# Acionadores_e_Atuadores.net
KiCad netlist of a schematic drawn in Altium Designer
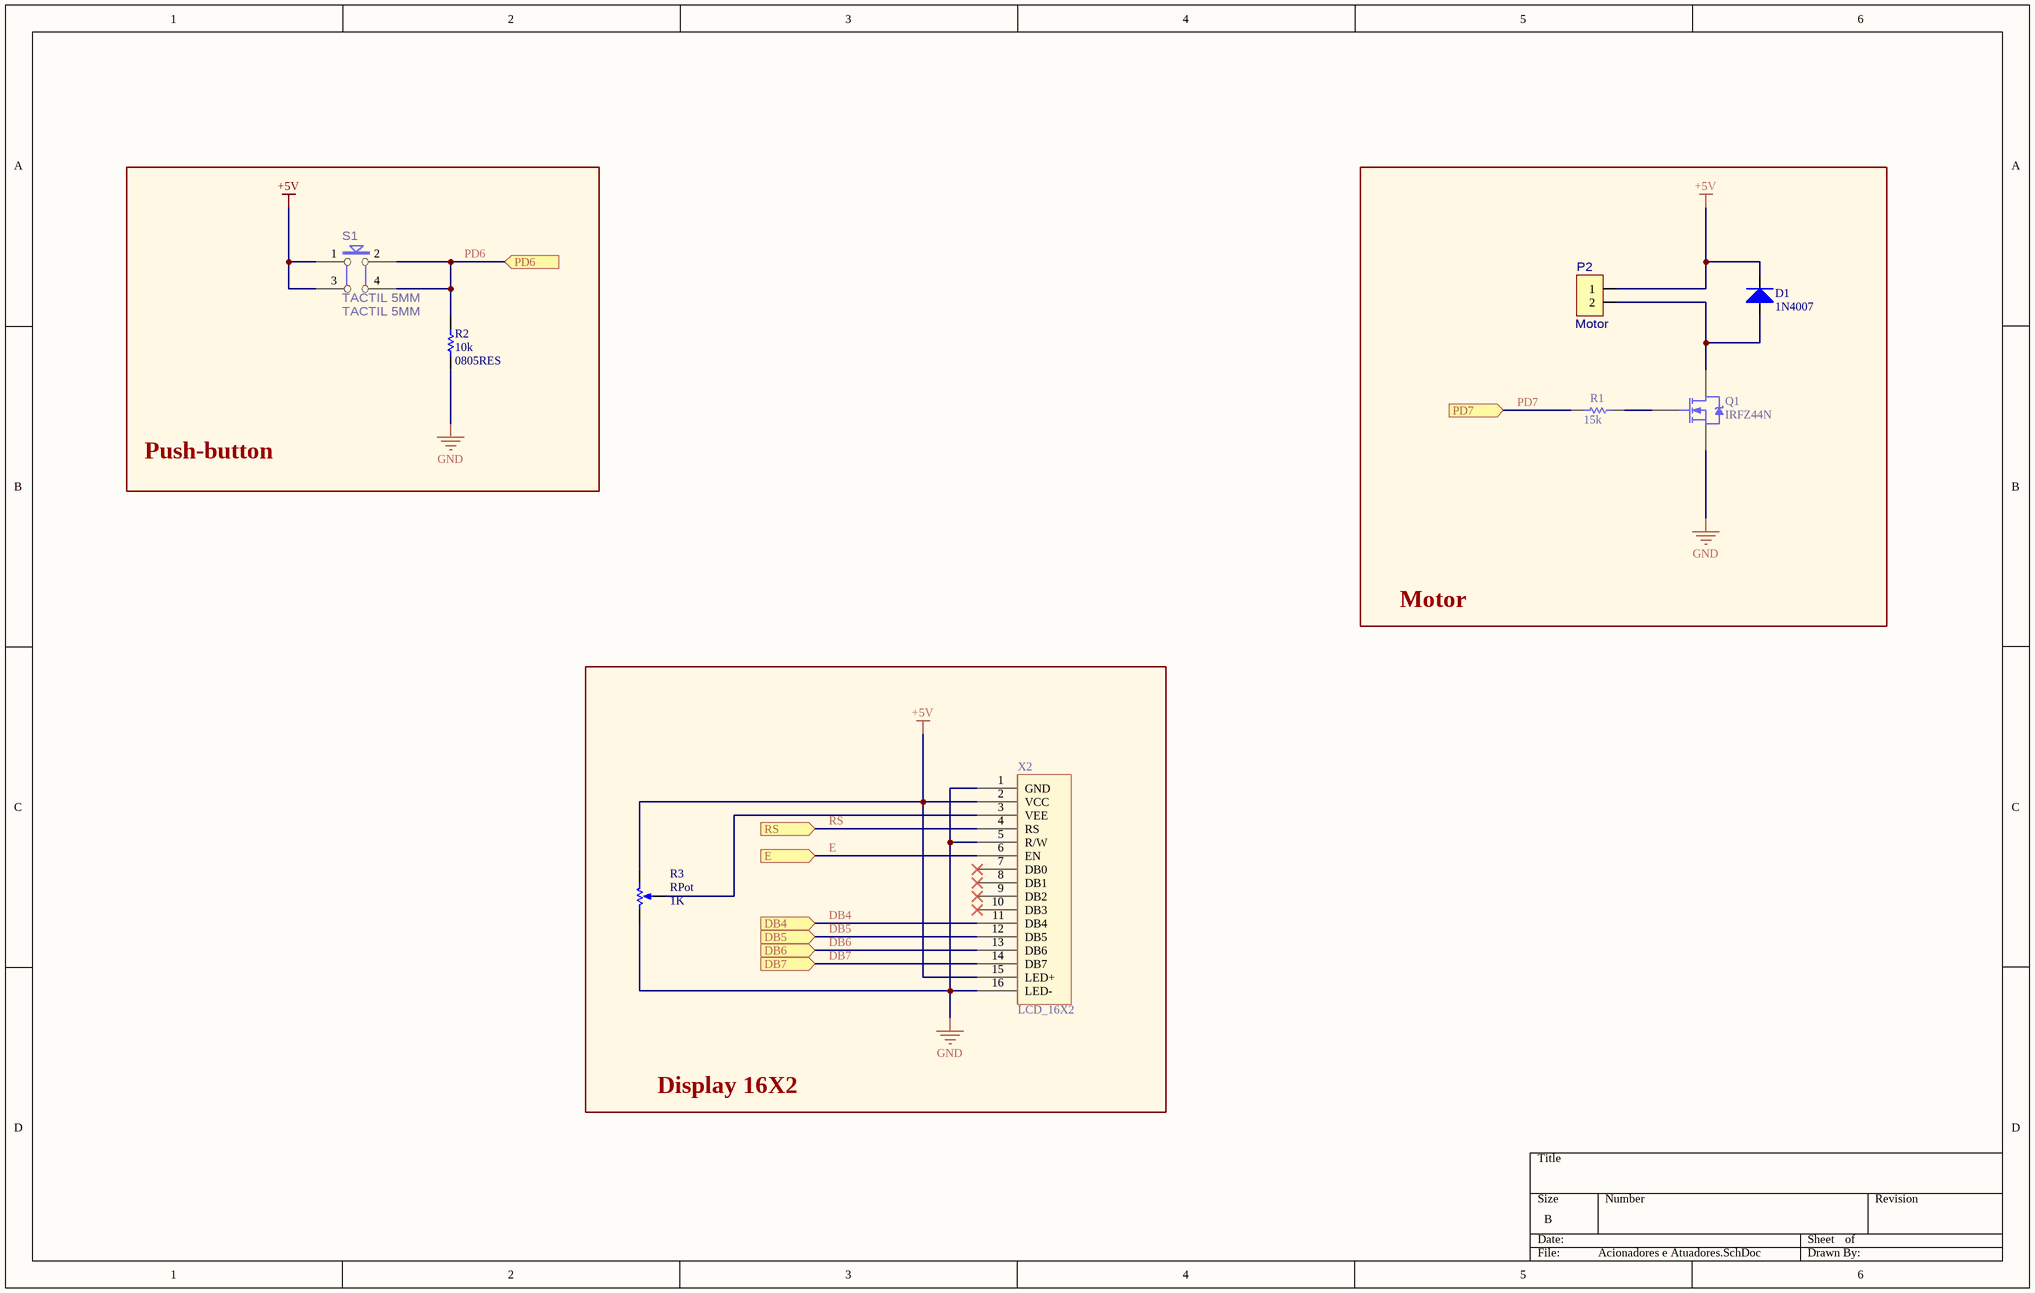
[diagram p0: Acionadores e Atuadores.SchDoc]

(export (version "E")
  (design (tool "Eeschema 10.0.6"))
  (components
    (comp (ref "D1")
      (value "1N4007")
      (footprint "SOD123 - duplicate")
      (description "Default Diode")
      (libsource (lib "Desafio_Hardware_Firmware_Nathania") (part "Diode"))
    )
    (comp (ref "P2")
      (value "KRE-2")
      (footprint "Motor")
      (libsource (lib "Desafio_Hardware_Firmware_Nathania") (part "CON2_2_2"))
    )
    (comp (ref "Q1")
      (value "IRFZ44N")
      (footprint "D2PAK_N")
      (description "HEXFET N-Channel Power MOSFET")
      (fields (field (name "PUBLISHER") "Altium Limited"))
      (libsource (lib "Desafio_Hardware_Firmware_Nathania") (part "IRF640S"))
    )
    (comp (ref "R1")
      (value "15k")
      (footprint "0805RES")
      (description "Resistor")
      (libsource (lib "Desafio_Hardware_Firmware_Nathania") (part "Res1"))
    )
    (comp (ref "R2")
      (value "10k")
      (footprint "0805RES")
      (description "Resistor")
      (libsource (lib "Desafio_Hardware_Firmware_Nathania") (part "Res1"))
    )
    (comp (ref "R3")
      (value "RPot")
      (footprint "Pot")
      (description "Potentiometer")
      (fields (field (name "ALTIUM_VALUE") "1K") (field (name "PUBLISHER") "Altium Limited"))
      (libsource (lib "Miscellaneous Devices") (part "RPot"))
    )
    (comp (ref "S1")
      (value "TACTIL 5MM")
      (footprint "TACTIL 5MM")
      (libsource (lib "Desafio_Hardware_Firmware_Nathania") (part "PUSH-BUTTON"))
    )
    (comp (ref "X2")
      (value "LCD_16X2")
      (footprint "LCD16X2")
      (libsource (lib "Desafio_Hardware_Firmware_Nathania") (part "LCD_16X2"))
    )
  )
  (nets
    (net (code "1") (name "+5V") (class "Default")
      (node (ref "D1") (pin "2") (pinfunction "K_2") (pintype "passive"))
      (node (ref "P2") (pin "1") (pinfunction "1_1") (pintype "passive"))
      (node (ref "R3") (pin "1") (pinfunction "TOP_1") (pintype "passive"))
      (node (ref "S1") (pin "1") (pintype "passive"))
      (node (ref "S1") (pin "3") (pintype "passive"))
      (node (ref "X2") (pin "15") (pinfunction "LED+_15") (pintype "passive"))
      (node (ref "X2") (pin "2") (pinfunction "VCC_2") (pintype "passive"))
    )
    (net (code "2") (name "/DB4") (class "Default")
      (node (ref "X2") (pin "11") (pinfunction "DB4_11") (pintype "passive"))
    )
    (net (code "3") (name "/DB5") (class "Default")
      (node (ref "X2") (pin "12") (pinfunction "DB5_12") (pintype "passive"))
    )
    (net (code "4") (name "/DB6") (class "Default")
      (node (ref "X2") (pin "13") (pinfunction "DB6_13") (pintype "passive"))
    )
    (net (code "5") (name "/DB7") (class "Default")
      (node (ref "X2") (pin "14") (pinfunction "DB7_14") (pintype "passive"))
    )
    (net (code "6") (name "/E") (class "Default")
      (node (ref "X2") (pin "6") (pinfunction "EN_6") (pintype "passive"))
    )
    (net (code "7") (name "/PD6") (class "Default")
      (node (ref "R2") (pin "2") (pinfunction "2_2") (pintype "passive"))
      (node (ref "S1") (pin "2") (pintype "passive"))
      (node (ref "S1") (pin "4") (pintype "passive"))
    )
    (net (code "8") (name "/PD7") (class "Default")
      (node (ref "R1") (pin "1") (pinfunction "1_1") (pintype "passive"))
    )
    (net (code "9") (name "/RS") (class "Default")
      (node (ref "X2") (pin "4") (pinfunction "RS_4") (pintype "passive"))
    )
    (net (code "10") (name "GND") (class "Default")
      (node (ref "Q1") (pin "3") (pinfunction "S_3") (pintype "passive"))
      (node (ref "R2") (pin "1") (pinfunction "1_1") (pintype "passive"))
      (node (ref "R3") (pin "2") (pinfunction "BOT_2") (pintype "passive"))
      (node (ref "X2") (pin "1") (pinfunction "GND_1") (pintype "passive"))
      (node (ref "X2") (pin "16") (pinfunction "LED-_16") (pintype "passive"))
      (node (ref "X2") (pin "5") (pinfunction "R/W_5") (pintype "passive"))
    )
    (net (code "11") (name "Net-(D1-A)") (class "Default")
      (node (ref "D1") (pin "1") (pinfunction "A_1") (pintype "passive"))
      (node (ref "P2") (pin "2") (pinfunction "2_2") (pintype "passive"))
      (node (ref "Q1") (pin "2") (pinfunction "D_2") (pintype "passive"))
    )
    (net (code "12") (name "Net-(Q1-G)") (class "Default")
      (node (ref "Q1") (pin "1") (pinfunction "G_1") (pintype "passive"))
      (node (ref "R1") (pin "2") (pinfunction "2_2") (pintype "passive"))
    )
    (net (code "13") (name "Net-(R3-TAP)") (class "Default")
      (node (ref "R3") (pin "3") (pinfunction "TAP_3") (pintype "passive"))
      (node (ref "X2") (pin "3") (pinfunction "VEE_3") (pintype "passive"))
    )
    (net (code "14") (name "unconnected-(X2-DB0-Pad7)") (class "Default")
      (node (ref "X2") (pin "7") (pinfunction "DB0_7") (pintype "passive+no_connect"))
    )
    (net (code "15") (name "unconnected-(X2-DB1-Pad8)") (class "Default")
      (node (ref "X2") (pin "8") (pinfunction "DB1_8") (pintype "passive+no_connect"))
    )
    (net (code "16") (name "unconnected-(X2-DB2-Pad9)") (class "Default")
      (node (ref "X2") (pin "9") (pinfunction "DB2_9") (pintype "passive+no_connect"))
    )
    (net (code "17") (name "unconnected-(X2-DB3-Pad10)") (class "Default")
      (node (ref "X2") (pin "10") (pinfunction "DB3_10") (pintype "passive+no_connect"))
    )
  )
)
